# rpi_hat.net
KiCad netlist of a schematic drawn in EAGLE
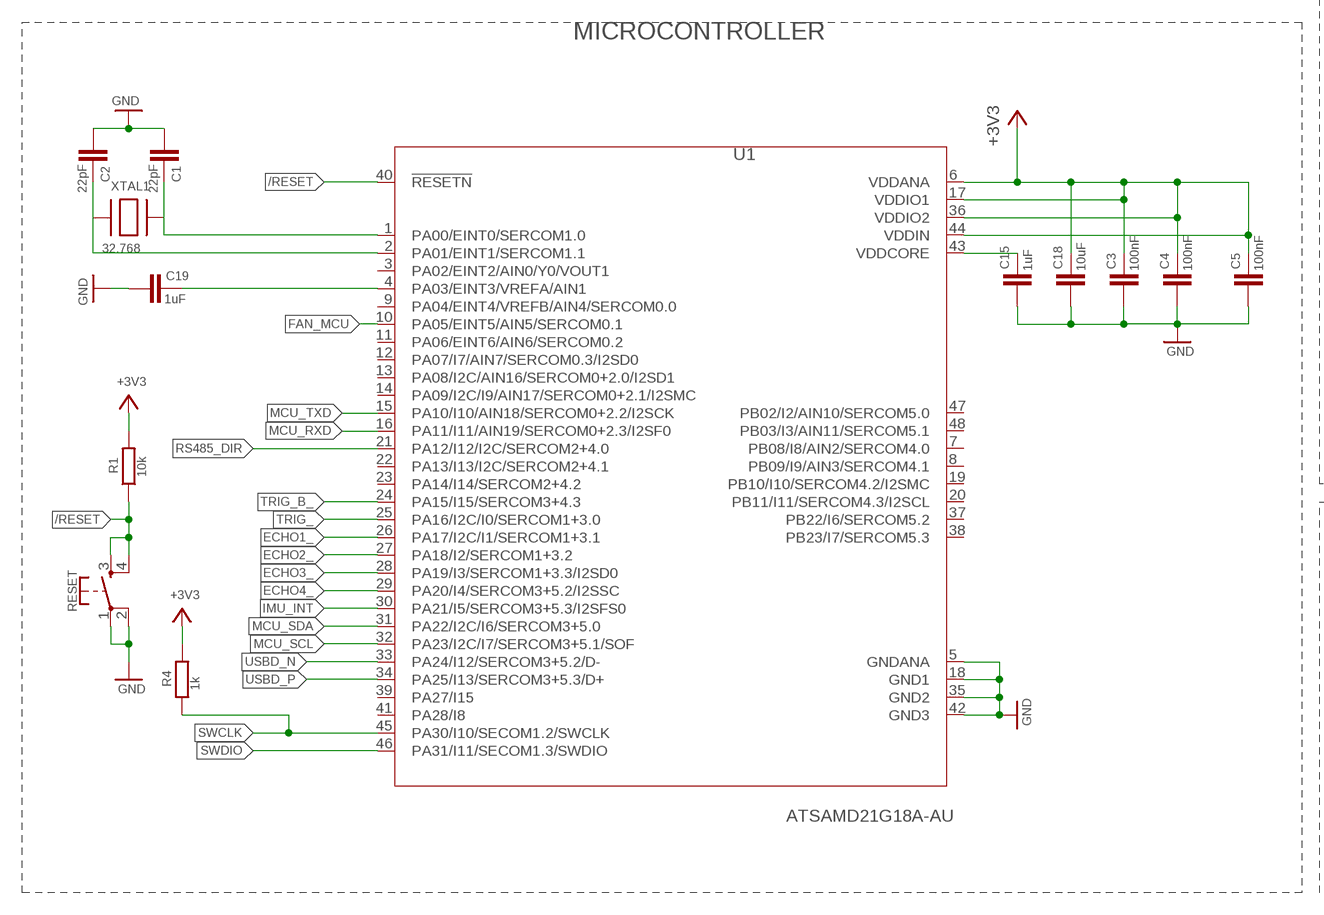
[diagram p0: schematic, sheet 1, part 1 of 2]
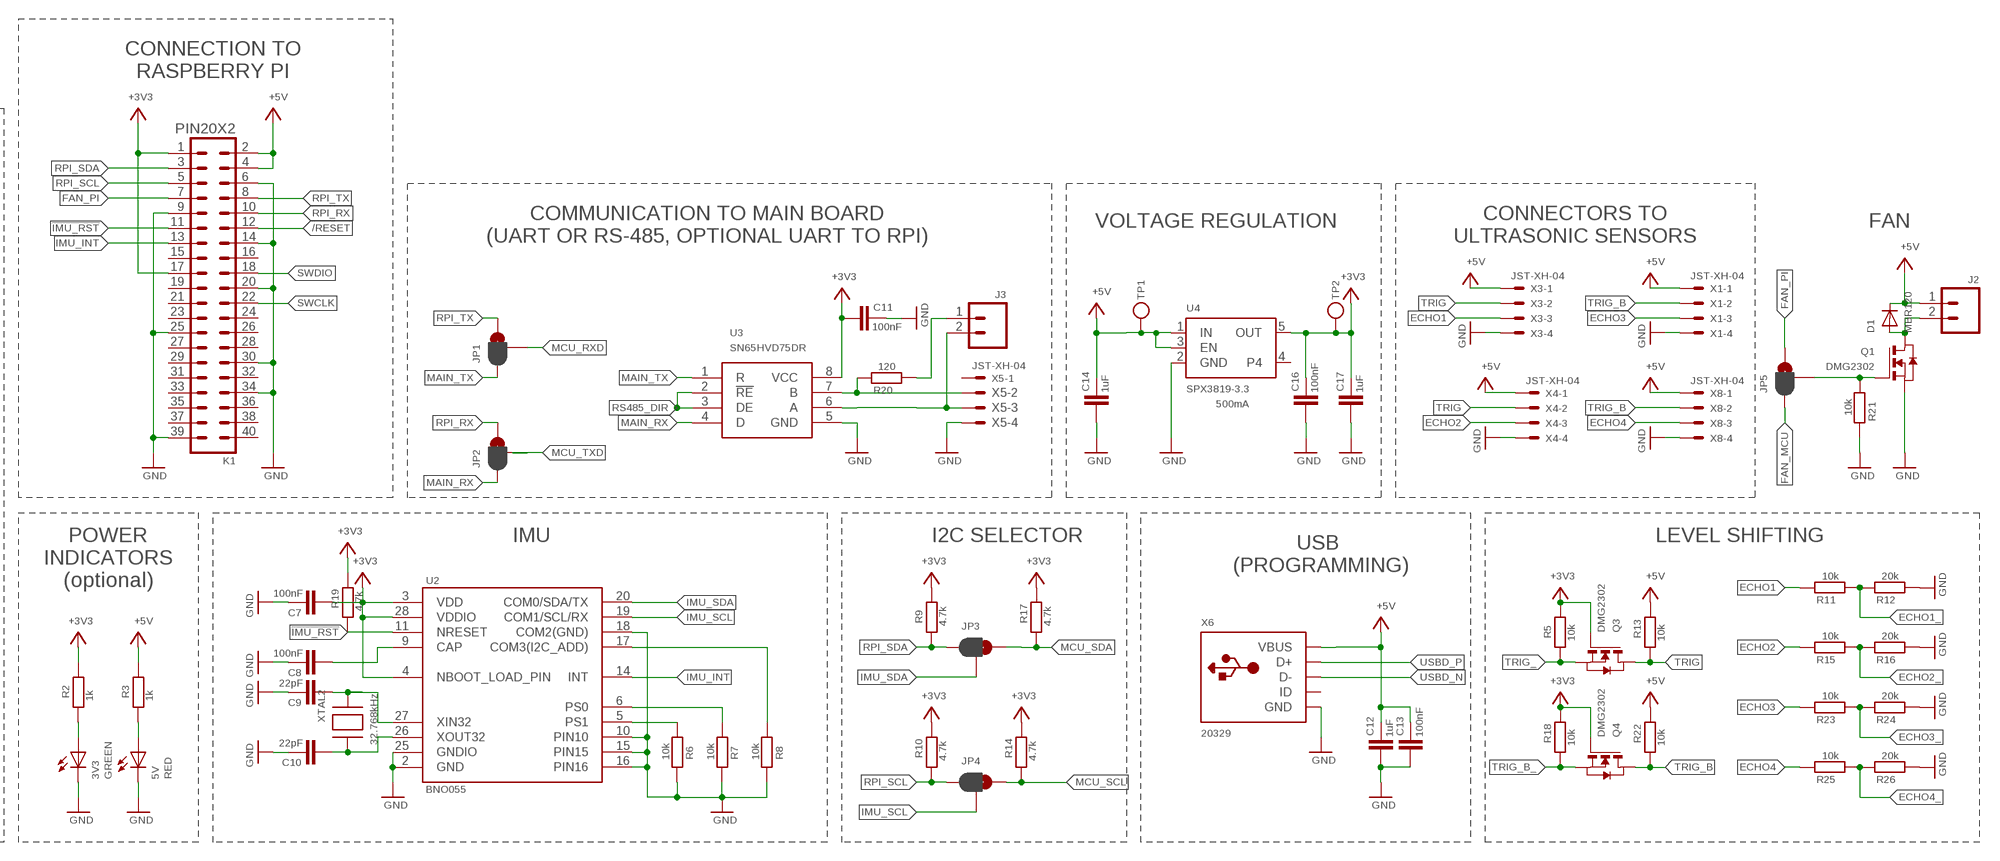
[diagram p1: schematic, sheet 1, part 2 of 2]

(export (version "E")
  (design (tool "Eeschema 10.0.6"))
  (components
    (comp (ref "3V3")
      (value "GREEN")
      (footprint "eagle-import:CHIP-LED0603")
      (libsource (lib "eagle-import") (part "LEDCHIP-LED0603"))
    )
    (comp (ref "5V")
      (value "RED")
      (footprint "eagle-import:CHIP-LED0603")
      (libsource (lib "eagle-import") (part "LEDCHIP-LED0603"))
    )
    (comp (ref "C1")
      (value "22pF")
      (footprint "eagle-import:C0402")
      (libsource (lib "eagle-import") (part "C-EUC0402"))
    )
    (comp (ref "C2")
      (value "22pF")
      (footprint "eagle-import:C0402")
      (libsource (lib "eagle-import") (part "C-EUC0402"))
    )
    (comp (ref "C3")
      (value "100nF")
      (footprint "eagle-import:C0402")
      (libsource (lib "eagle-import") (part "C-EUC0402"))
    )
    (comp (ref "C4")
      (value "100nF")
      (footprint "eagle-import:C0402")
      (libsource (lib "eagle-import") (part "C-EUC0402"))
    )
    (comp (ref "C5")
      (value "100nF")
      (footprint "eagle-import:C0402")
      (libsource (lib "eagle-import") (part "C-EUC0402"))
    )
    (comp (ref "C7")
      (value "100nF")
      (footprint "eagle-import:C0402")
      (libsource (lib "eagle-import") (part "C-EUC0402"))
    )
    (comp (ref "C8")
      (value "100nF")
      (footprint "eagle-import:C0402")
      (libsource (lib "eagle-import") (part "C-EUC0402"))
    )
    (comp (ref "C9")
      (value "22pF")
      (footprint "eagle-import:C0402")
      (libsource (lib "eagle-import") (part "C-EUC0402"))
    )
    (comp (ref "C10")
      (value "22pF")
      (footprint "eagle-import:C0402")
      (libsource (lib "eagle-import") (part "C-EUC0402"))
    )
    (comp (ref "C11")
      (value "100nF")
      (footprint "eagle-import:C0402")
      (libsource (lib "eagle-import") (part "C-EUC0402"))
    )
    (comp (ref "C12")
      (value "1uF")
      (footprint "eagle-import:C0402")
      (libsource (lib "eagle-import") (part "C-EUC0402"))
    )
    (comp (ref "C13")
      (value "100nF")
      (footprint "eagle-import:C0402")
      (libsource (lib "eagle-import") (part "C-EUC0402"))
    )
    (comp (ref "C14")
      (value "1uF")
      (footprint "eagle-import:C0402")
      (libsource (lib "eagle-import") (part "C-EUC0402"))
    )
    (comp (ref "C15")
      (value "1uF")
      (footprint "eagle-import:C0402")
      (libsource (lib "eagle-import") (part "C-EUC0402"))
    )
    (comp (ref "C16")
      (value "100nF")
      (footprint "eagle-import:C0402")
      (libsource (lib "eagle-import") (part "C-EUC0402"))
    )
    (comp (ref "C17")
      (value "1uF")
      (footprint "eagle-import:C0402")
      (libsource (lib "eagle-import") (part "C-EUC0402"))
    )
    (comp (ref "C18")
      (value "10uF")
      (footprint "eagle-import:C0402")
      (libsource (lib "eagle-import") (part "C-EUC0402"))
    )
    (comp (ref "C19")
      (value "1uF")
      (footprint "eagle-import:C0402")
      (libsource (lib "eagle-import") (part "C-EUC0402"))
    )
    (comp (ref "D1")
      (value "MBR120")
      (footprint "eagle-import:SOD-123")
      (libsource (lib "eagle-import") (part "DIODESOD-123"))
    )
    (comp (ref "J2")
      (value "CONN_02")
      (footprint "eagle-import:1X02")
      (libsource (lib "eagle-import") (part "CONN_02"))
    )
    (comp (ref "J3")
      (value "CONN_02")
      (footprint "eagle-import:1X02")
      (libsource (lib "eagle-import") (part "CONN_02"))
    )
    (comp (ref "JP1")
      (value "SPARKFUN-PASSIVES_JUMPER_PAD-3-1&2_NC_BY_PASTE")
      (footprint "eagle-import:SPARKFUN-PASSIVES_PAD-HUMPER-3-1&2_NC_BY_PASTE_YES_SILK_FULL_BOX")
      (libsource (lib "eagle-import") (part "SPARKFUN-PASSIVES_JUMPER_PAD-3-1&2_NC_BY_PASTE"))
    )
    (comp (ref "JP2")
      (value "SPARKFUN-PASSIVES_JUMPER_PAD-3-1&2_NC_BY_PASTE")
      (footprint "eagle-import:SPARKFUN-PASSIVES_PAD-HUMPER-3-1&2_NC_BY_PASTE_YES_SILK_FULL_BOX")
      (libsource (lib "eagle-import") (part "SPARKFUN-PASSIVES_JUMPER_PAD-3-1&2_NC_BY_PASTE"))
    )
    (comp (ref "JP3")
      (value "SPARKFUN-PASSIVES_JUMPER_PAD-3-1&2_NC_BY_PASTE")
      (footprint "eagle-import:SPARKFUN-PASSIVES_PAD-HUMPER-3-1&2_NC_BY_PASTE_YES_SILK_FULL_BOX")
      (libsource (lib "eagle-import") (part "SPARKFUN-PASSIVES_JUMPER_PAD-3-1&2_NC_BY_PASTE"))
    )
    (comp (ref "JP4")
      (value "SPARKFUN-PASSIVES_JUMPER_PAD-3-1&2_NC_BY_PASTE")
      (footprint "eagle-import:SPARKFUN-PASSIVES_PAD-HUMPER-3-1&2_NC_BY_PASTE_YES_SILK_FULL_BOX")
      (libsource (lib "eagle-import") (part "SPARKFUN-PASSIVES_JUMPER_PAD-3-1&2_NC_BY_PASTE"))
    )
    (comp (ref "JP5")
      (value "SPARKFUN-PASSIVES_JUMPER_PAD-3-1&2_NC_BY_PASTE")
      (footprint "eagle-import:SPARKFUN-PASSIVES_PAD-HUMPER-3-1&2_NC_BY_PASTE_YES_SILK_FULL_BOX")
      (libsource (lib "eagle-import") (part "SPARKFUN-PASSIVES_JUMPER_PAD-3-1&2_NC_BY_PASTE"))
    )
    (comp (ref "K1")
      (value "PIN20X2")
      (footprint "eagle-import:PIN_20X2")
      (libsource (lib "eagle-import") (part "PIN20X2"))
    )
    (comp (ref "Q1")
      (value "DMG2302")
      (footprint "eagle-import:SOT-23")
      (libsource (lib "eagle-import") (part "NMOS-SOT23"))
    )
    (comp (ref "Q3")
      (value "DMG2302")
      (footprint "eagle-import:SOT-23")
      (libsource (lib "eagle-import") (part "NMOS-SOT23"))
    )
    (comp (ref "Q4")
      (value "DMG2302")
      (footprint "eagle-import:SOT-23")
      (libsource (lib "eagle-import") (part "NMOS-SOT23"))
    )
    (comp (ref "R1")
      (value "10k")
      (footprint "eagle-import:R0402")
      (libsource (lib "eagle-import") (part "R-EU_R0402"))
    )
    (comp (ref "R2")
      (value "1k")
      (footprint "eagle-import:R0402")
      (libsource (lib "eagle-import") (part "R-EU_R0402"))
    )
    (comp (ref "R3")
      (value "1k")
      (footprint "eagle-import:R0402")
      (libsource (lib "eagle-import") (part "R-EU_R0402"))
    )
    (comp (ref "R4")
      (value "1k")
      (footprint "eagle-import:R0402")
      (libsource (lib "eagle-import") (part "R-EU_R0402"))
    )
    (comp (ref "R5")
      (value "10k")
      (footprint "eagle-import:R0402")
      (libsource (lib "eagle-import") (part "R-EU_R0402"))
    )
    (comp (ref "R6")
      (value "10k")
      (footprint "eagle-import:R0402")
      (libsource (lib "eagle-import") (part "R-EU_R0402"))
    )
    (comp (ref "R7")
      (value "10k")
      (footprint "eagle-import:R0402")
      (libsource (lib "eagle-import") (part "R-EU_R0402"))
    )
    (comp (ref "R8")
      (value "10k")
      (footprint "eagle-import:R0402")
      (libsource (lib "eagle-import") (part "R-EU_R0402"))
    )
    (comp (ref "R9")
      (value "4.7k")
      (footprint "eagle-import:R0402")
      (libsource (lib "eagle-import") (part "R-EU_R0402"))
    )
    (comp (ref "R10")
      (value "4.7k")
      (footprint "eagle-import:R0402")
      (libsource (lib "eagle-import") (part "R-EU_R0402"))
    )
    (comp (ref "R11")
      (value "10k")
      (footprint "eagle-import:R0402")
      (libsource (lib "eagle-import") (part "R-EU_R0402"))
    )
    (comp (ref "R12")
      (value "20k")
      (footprint "eagle-import:R0402")
      (libsource (lib "eagle-import") (part "R-EU_R0402"))
    )
    (comp (ref "R13")
      (value "10k")
      (footprint "eagle-import:R0402")
      (libsource (lib "eagle-import") (part "R-EU_R0402"))
    )
    (comp (ref "R14")
      (value "4.7k")
      (footprint "eagle-import:R0402")
      (libsource (lib "eagle-import") (part "R-EU_R0402"))
    )
    (comp (ref "R15")
      (value "10k")
      (footprint "eagle-import:R0402")
      (libsource (lib "eagle-import") (part "R-EU_R0402"))
    )
    (comp (ref "R16")
      (value "20k")
      (footprint "eagle-import:R0402")
      (libsource (lib "eagle-import") (part "R-EU_R0402"))
    )
    (comp (ref "R17")
      (value "4.7k")
      (footprint "eagle-import:R0402")
      (libsource (lib "eagle-import") (part "R-EU_R0402"))
    )
    (comp (ref "R18")
      (value "10k")
      (footprint "eagle-import:R0402")
      (libsource (lib "eagle-import") (part "R-EU_R0402"))
    )
    (comp (ref "R19")
      (value "4.7k")
      (footprint "eagle-import:R0402")
      (libsource (lib "eagle-import") (part "R-EU_R0402"))
    )
    (comp (ref "R20")
      (value "120")
      (footprint "eagle-import:R0402")
      (libsource (lib "eagle-import") (part "R-EU_R0402"))
    )
    (comp (ref "R21")
      (value "10k")
      (footprint "eagle-import:R0402")
      (libsource (lib "eagle-import") (part "R-EU_R0402"))
    )
    (comp (ref "R22")
      (value "10k")
      (footprint "eagle-import:R0402")
      (libsource (lib "eagle-import") (part "R-EU_R0402"))
    )
    (comp (ref "R23")
      (value "10k")
      (footprint "eagle-import:R0402")
      (libsource (lib "eagle-import") (part "R-EU_R0402"))
    )
    (comp (ref "R24")
      (value "20k")
      (footprint "eagle-import:R0402")
      (libsource (lib "eagle-import") (part "R-EU_R0402"))
    )
    (comp (ref "R25")
      (value "10k")
      (footprint "eagle-import:R0402")
      (libsource (lib "eagle-import") (part "R-EU_R0402"))
    )
    (comp (ref "R26")
      (value "20k")
      (footprint "eagle-import:R0402")
      (libsource (lib "eagle-import") (part "R-EU_R0402"))
    )
    (comp (ref "RESET")
      (value "MOMENTARY-SWITCH-SPST-2-SMD-4.6X2.8MM")
      (footprint "eagle-import:TACTILE_SWITCH_SMD_4.6X2.8MM")
      (libsource (lib "eagle-import") (part "MOMENTARY-SWITCH-SPST-2-SMD-4.6X2.8MM"))
    )
    (comp (ref "TP1")
      (value "MICROBUILDER_TESTPOINTROUND1MM")
      (footprint "eagle-import:MICROBUILDER_TESTPOINT_ROUND_1MM")
      (libsource (lib "eagle-import") (part "MICROBUILDER_TESTPOINTROUND1MM"))
    )
    (comp (ref "TP2")
      (value "MICROBUILDER_TESTPOINTROUND1MM")
      (footprint "eagle-import:MICROBUILDER_TESTPOINT_ROUND_1MM")
      (libsource (lib "eagle-import") (part "MICROBUILDER_TESTPOINTROUND1MM"))
    )
    (comp (ref "U1")
      (value "ATSAMD21G18A-AU")
      (footprint "eagle-import:QFP50P900X900X120-48N")
      (fields (field (name "MF") "Microchip"))
      (libsource (lib "eagle-import") (part "ATSAMD21G18A-AU"))
    )
    (comp (ref "U2")
      (value "BNO055")
      (footprint "eagle-import:LGA28R50P4X10_380X520X100")
      (fields (field (name "MF") "Bosch"))
      (libsource (lib "eagle-import") (part "BNO055"))
    )
    (comp (ref "U3")
      (value "SN65HVD75DR")
      (footprint "eagle-import:SOIC127P600X175-8N")
      (fields (field (name "MF") "Texas Instruments"))
      (libsource (lib "eagle-import") (part "SN65HVD75DR"))
    )
    (comp (ref "U4")
      (value "SPX3819-3.3")
      (footprint "eagle-import:SOT23-5")
      (libsource (lib "eagle-import") (part "VREG_SOT23-5"))
    )
    (comp (ref "X1")
      (value "JST-XH-04")
      (footprint "eagle-import:JST-XH-04-PACKAGE-ROUND-PAD")
      (libsource (lib "eagle-import") (part "JST-XH-04-PIN-ROUND-PAD"))
    )
    (comp (ref "X3")
      (value "JST-XH-04")
      (footprint "eagle-import:JST-XH-04-PACKAGE-ROUND-PAD")
      (libsource (lib "eagle-import") (part "JST-XH-04-PIN-ROUND-PAD"))
    )
    (comp (ref "X4")
      (value "JST-XH-04")
      (footprint "eagle-import:JST-XH-04-PACKAGE-ROUND-PAD")
      (libsource (lib "eagle-import") (part "JST-XH-04-PIN-ROUND-PAD"))
    )
    (comp (ref "X5")
      (value "JST-XH-04")
      (footprint "eagle-import:JST-XH-04-PACKAGE-ROUND-PAD")
      (libsource (lib "eagle-import") (part "JST-XH-04-PIN-ROUND-PAD"))
    )
    (comp (ref "X6")
      (value "20329")
      (footprint "eagle-import:4UCONN_20329_V2")
      (libsource (lib "eagle-import") (part "USB_MICRO_20329_V2"))
    )
    (comp (ref "X8")
      (value "JST-XH-04")
      (footprint "eagle-import:JST-XH-04-PACKAGE-ROUND-PAD")
      (libsource (lib "eagle-import") (part "JST-XH-04-PIN-ROUND-PAD"))
    )
    (comp (ref "XTAL1")
      (value "32.768")
      (footprint "eagle-import:XTAL3215")
      (libsource (lib "eagle-import") (part "XTAL-3.2X1.5"))
    )
    (comp (ref "XTAL2")
      (value "32.768kHz")
      (footprint "eagle-import:ADAFRUIT2_XTAL3215")
      (libsource (lib "eagle-import") (part "ADAFRUIT2_XTAL-3.2X1.5"))
    )
  )
  (nets
    (net (code "1") (name "+3V3") (class "Default")
      (node (ref "C11") (pin "2") (pinfunction "2_2") (pintype "passive"))
      (node (ref "C16") (pin "1") (pinfunction "1_1") (pintype "passive"))
      (node (ref "C17") (pin "1") (pinfunction "1_1") (pintype "passive"))
      (node (ref "C18") (pin "1") (pinfunction "1_1") (pintype "passive"))
      (node (ref "C3") (pin "1") (pinfunction "1_1") (pintype "passive"))
      (node (ref "C4") (pin "1") (pinfunction "1_1") (pintype "passive"))
      (node (ref "C5") (pin "1") (pinfunction "1_1") (pintype "passive"))
      (node (ref "C7") (pin "2") (pinfunction "2_2") (pintype "passive"))
      (node (ref "K1") (pin "1") (pinfunction "1_1") (pintype "passive"))
      (node (ref "K1") (pin "17") (pinfunction "17_17") (pintype "passive"))
      (node (ref "Q3") (pin "G") (pinfunction "G_G") (pintype "passive"))
      (node (ref "Q4") (pin "G") (pinfunction "G_G") (pintype "passive"))
      (node (ref "R1") (pin "2") (pinfunction "2_2") (pintype "passive"))
      (node (ref "R10") (pin "2") (pinfunction "2_2") (pintype "passive"))
      (node (ref "R14") (pin "2") (pinfunction "2_2") (pintype "passive"))
      (node (ref "R17") (pin "2") (pinfunction "2_2") (pintype "passive"))
      (node (ref "R18") (pin "2") (pinfunction "2_2") (pintype "passive"))
      (node (ref "R19") (pin "2") (pinfunction "2_2") (pintype "passive"))
      (node (ref "R2") (pin "2") (pinfunction "2_2") (pintype "passive"))
      (node (ref "R4") (pin "2") (pinfunction "2_2") (pintype "passive"))
      (node (ref "R5") (pin "2") (pinfunction "2_2") (pintype "passive"))
      (node (ref "R9") (pin "2") (pinfunction "2_2") (pintype "passive"))
      (node (ref "TP2") (pin "P$1") (pinfunction "P$1_P$1") (pintype "bidirectional"))
      (node (ref "U1") (pin "17") (pinfunction "VDDIO1_17") (pintype "power_in"))
      (node (ref "U1") (pin "36") (pinfunction "VDDIO2_36") (pintype "power_in"))
      (node (ref "U1") (pin "44") (pinfunction "VDDIN_44") (pintype "power_in"))
      (node (ref "U1") (pin "6") (pinfunction "VDDANA_6") (pintype "power_in"))
      (node (ref "U2") (pin "28") (pinfunction "VDDIO_28") (pintype "power_in"))
      (node (ref "U2") (pin "3") (pinfunction "VDD_3") (pintype "power_in"))
      (node (ref "U2") (pin "4") (pinfunction "NBOOT_LOAD_PIN_4") (pintype "bidirectional"))
      (node (ref "U3") (pin "8") (pinfunction "VCC_8") (pintype "bidirectional"))
      (node (ref "U4") (pin "5") (pinfunction "OUT_5") (pintype "power_in"))
    )
    (net (code "2") (name "+5V") (class "Default")
      (node (ref "C12") (pin "1") (pinfunction "1_1") (pintype "passive"))
      (node (ref "C13") (pin "1") (pinfunction "1_1") (pintype "passive"))
      (node (ref "C14") (pin "1") (pinfunction "1_1") (pintype "passive"))
      (node (ref "D1") (pin "C") (pinfunction "C_C") (pintype "passive"))
      (node (ref "J2") (pin "1") (pinfunction "1_1") (pintype "passive"))
      (node (ref "K1") (pin "2") (pinfunction "2_2") (pintype "passive"))
      (node (ref "K1") (pin "4") (pinfunction "4_4") (pintype "passive"))
      (node (ref "R13") (pin "2") (pinfunction "2_2") (pintype "passive"))
      (node (ref "R22") (pin "2") (pinfunction "2_2") (pintype "passive"))
      (node (ref "R3") (pin "2") (pinfunction "2_2") (pintype "passive"))
      (node (ref "TP1") (pin "P$1") (pinfunction "P$1_P$1") (pintype "bidirectional"))
      (node (ref "U4") (pin "1") (pinfunction "IN_1") (pintype "power_in"))
      (node (ref "U4") (pin "3") (pinfunction "EN_3") (pintype "input"))
      (node (ref "X1") (pin "1") (pinfunction "S_1") (pintype "passive"))
      (node (ref "X3") (pin "1") (pinfunction "S_1") (pintype "passive"))
      (node (ref "X4") (pin "1") (pinfunction "S_1") (pintype "passive"))
      (node (ref "X6") (pin "VBUS") (pinfunction "VBUS_VBUS") (pintype "power_in"))
      (node (ref "X8") (pin "1") (pinfunction "S_1") (pintype "passive"))
    )
    (net (code "3") (name "/~{IMU_RST}") (class "Default")
      (node (ref "K1") (pin "11") (pinfunction "11_11") (pintype "passive"))
      (node (ref "R19") (pin "1") (pinfunction "1_1") (pintype "passive"))
      (node (ref "U2") (pin "11") (pinfunction "NRESET_11") (pintype "input"))
    )
    (net (code "4") (name "ECHO1") (class "Default")
      (node (ref "R11") (pin "2") (pinfunction "2_2") (pintype "passive"))
      (node (ref "X3") (pin "3") (pinfunction "S_3") (pintype "passive"))
    )
    (net (code "5") (name "ECHO1_") (class "Default")
      (node (ref "R11") (pin "1") (pinfunction "1_1") (pintype "passive"))
      (node (ref "R12") (pin "2") (pinfunction "2_2") (pintype "passive"))
      (node (ref "U1") (pin "26") (pinfunction "PA17/I2C/I1/SERCOM1+3.1_26") (pintype "bidirectional"))
    )
    (net (code "6") (name "ECHO2") (class "Default")
      (node (ref "R15") (pin "2") (pinfunction "2_2") (pintype "passive"))
      (node (ref "X4") (pin "3") (pinfunction "S_3") (pintype "passive"))
    )
    (net (code "7") (name "ECHO2_") (class "Default")
      (node (ref "R15") (pin "1") (pinfunction "1_1") (pintype "passive"))
      (node (ref "R16") (pin "2") (pinfunction "2_2") (pintype "passive"))
      (node (ref "U1") (pin "27") (pinfunction "PA18/I2/SERCOM1+3.2_27") (pintype "bidirectional"))
    )
    (net (code "8") (name "ECHO3") (class "Default")
      (node (ref "R23") (pin "2") (pinfunction "2_2") (pintype "passive"))
      (node (ref "X1") (pin "3") (pinfunction "S_3") (pintype "passive"))
    )
    (net (code "9") (name "ECHO3_") (class "Default")
      (node (ref "R23") (pin "1") (pinfunction "1_1") (pintype "passive"))
      (node (ref "R24") (pin "2") (pinfunction "2_2") (pintype "passive"))
      (node (ref "U1") (pin "28") (pinfunction "PA19/I3/SERCOM1+3.3/I2SD0_28") (pintype "bidirectional"))
    )
    (net (code "10") (name "ECHO4") (class "Default")
      (node (ref "R25") (pin "2") (pinfunction "2_2") (pintype "passive"))
      (node (ref "X8") (pin "3") (pinfunction "S_3") (pintype "passive"))
    )
    (net (code "11") (name "ECHO4_") (class "Default")
      (node (ref "R25") (pin "1") (pinfunction "1_1") (pintype "passive"))
      (node (ref "R26") (pin "2") (pinfunction "2_2") (pintype "passive"))
      (node (ref "U1") (pin "29") (pinfunction "PA20/I4/SERCOM3+5.2/I2SSC_29") (pintype "bidirectional"))
    )
    (net (code "12") (name "FAN_MCU") (class "Default")
      (node (ref "JP5") (pin "1") (pinfunction "1_1") (pintype "passive"))
      (node (ref "U1") (pin "10") (pinfunction "PA05/EINT5/AIN5/SERCOM0.1_10") (pintype "bidirectional"))
    )
    (net (code "13") (name "FAN_PI") (class "Default")
      (node (ref "JP5") (pin "3") (pinfunction "3_3") (pintype "passive"))
      (node (ref "K1") (pin "7") (pinfunction "7_7") (pintype "passive"))
    )
    (net (code "14") (name "GND") (class "Default")
      (node (ref "3V3") (pin "C") (pinfunction "C_C") (pintype "passive"))
      (node (ref "5V") (pin "C") (pinfunction "C_C") (pintype "passive"))
      (node (ref "C1") (pin "2") (pinfunction "2_2") (pintype "passive"))
      (node (ref "C10") (pin "1") (pinfunction "1_1") (pintype "passive"))
      (node (ref "C11") (pin "1") (pinfunction "1_1") (pintype "passive"))
      (node (ref "C12") (pin "2") (pinfunction "2_2") (pintype "passive"))
      (node (ref "C13") (pin "2") (pinfunction "2_2") (pintype "passive"))
      (node (ref "C14") (pin "2") (pinfunction "2_2") (pintype "passive"))
      (node (ref "C15") (pin "2") (pinfunction "2_2") (pintype "passive"))
      (node (ref "C16") (pin "2") (pinfunction "2_2") (pintype "passive"))
      (node (ref "C17") (pin "2") (pinfunction "2_2") (pintype "passive"))
      (node (ref "C18") (pin "2") (pinfunction "2_2") (pintype "passive"))
      (node (ref "C19") (pin "2") (pinfunction "2_2") (pintype "passive"))
      (node (ref "C2") (pin "2") (pinfunction "2_2") (pintype "passive"))
      (node (ref "C3") (pin "2") (pinfunction "2_2") (pintype "passive"))
      (node (ref "C4") (pin "2") (pinfunction "2_2") (pintype "passive"))
      (node (ref "C5") (pin "2") (pinfunction "2_2") (pintype "passive"))
      (node (ref "C7") (pin "1") (pinfunction "1_1") (pintype "passive"))
      (node (ref "C8") (pin "1") (pinfunction "1_1") (pintype "passive"))
      (node (ref "C9") (pin "1") (pinfunction "1_1") (pintype "passive"))
      (node (ref "K1") (pin "14") (pinfunction "14_14") (pintype "passive"))
      (node (ref "K1") (pin "20") (pinfunction "20_20") (pintype "passive"))
      (node (ref "K1") (pin "25") (pinfunction "25_25") (pintype "passive"))
      (node (ref "K1") (pin "30") (pinfunction "30_30") (pintype "passive"))
      (node (ref "K1") (pin "34") (pinfunction "34_34") (pintype "passive"))
      (node (ref "K1") (pin "39") (pinfunction "39_39") (pintype "passive"))
      (node (ref "K1") (pin "6") (pinfunction "6_6") (pintype "passive"))
      (node (ref "K1") (pin "9") (pinfunction "9_9") (pintype "passive"))
      (node (ref "Q1") (pin "S") (pinfunction "S_S") (pintype "passive"))
      (node (ref "R12") (pin "1") (pinfunction "1_1") (pintype "passive"))
      (node (ref "R16") (pin "1") (pinfunction "1_1") (pintype "passive"))
      (node (ref "R21") (pin "2") (pinfunction "2_2") (pintype "passive"))
      (node (ref "R24") (pin "1") (pinfunction "1_1") (pintype "passive"))
      (node (ref "R26") (pin "1") (pinfunction "1_1") (pintype "passive"))
      (node (ref "R6") (pin "2") (pinfunction "2_2") (pintype "passive"))
      (node (ref "R7") (pin "2") (pinfunction "2_2") (pintype "passive"))
      (node (ref "R8") (pin "2") (pinfunction "2_2") (pintype "passive"))
      (node (ref "RESET") (pin "1") (pinfunction "1_1") (pintype "passive"))
      (node (ref "RESET") (pin "2") (pinfunction "2_2") (pintype "passive"))
      (node (ref "U1") (pin "18") (pinfunction "GND1_18") (pintype "power_in"))
      (node (ref "U1") (pin "35") (pinfunction "GND2_35") (pintype "power_in"))
      (node (ref "U1") (pin "42") (pinfunction "GND3_42") (pintype "power_in"))
      (node (ref "U1") (pin "5") (pinfunction "GNDANA_5") (pintype "power_in"))
      (node (ref "U2") (pin "10") (pinfunction "PIN10_10") (pintype "power_in"))
      (node (ref "U2") (pin "15") (pinfunction "PIN15_15") (pintype "power_in"))
      (node (ref "U2") (pin "16") (pinfunction "PIN16_16") (pintype "power_in"))
      (node (ref "U2") (pin "18") (pinfunction "COM2(GND)_18") (pintype "bidirectional"))
      (node (ref "U2") (pin "2") (pinfunction "GND_2") (pintype "power_in"))
      (node (ref "U2") (pin "25") (pinfunction "GNDIO_25") (pintype "power_in"))
      (node (ref "U3") (pin "5") (pinfunction "GND_5") (pintype "bidirectional"))
      (node (ref "U4") (pin "2") (pinfunction "GND_2") (pintype "power_in"))
      (node (ref "X1") (pin "4") (pinfunction "S_4") (pintype "passive"))
      (node (ref "X3") (pin "4") (pinfunction "S_4") (pintype "passive"))
      (node (ref "X4") (pin "4") (pinfunction "S_4") (pintype "passive"))
      (node (ref "X5") (pin "4") (pinfunction "S_4") (pintype "passive"))
      (node (ref "X6") (pin "BASE@1") (pinfunction "GND_BASE@1") (pintype "power_in"))
      (node (ref "X6") (pin "BASE@2") (pinfunction "GND_BASE@2") (pintype "power_in"))
      (node (ref "X6") (pin "GND") (pinfunction "GND_GND") (pintype "power_in"))
      (node (ref "X6") (pin "SPRT@1") (pinfunction "GND_SPRT@1") (pintype "power_in"))
      (node (ref "X6") (pin "SPRT@2") (pinfunction "GND_SPRT@2") (pintype "power_in"))
      (node (ref "X6") (pin "SPRT@3") (pinfunction "GND_SPRT@3") (pintype "power_in"))
      (node (ref "X6") (pin "SPRT@4") (pinfunction "GND_SPRT@4") (pintype "power_in"))
      (node (ref "X8") (pin "4") (pinfunction "S_4") (pintype "passive"))
    )
    (net (code "15") (name "IMU_INT") (class "Default")
      (node (ref "K1") (pin "13") (pinfunction "13_13") (pintype "passive"))
      (node (ref "U1") (pin "30") (pinfunction "PA21/I5/SERCOM3+5.3/I2SFS0_30") (pintype "bidirectional"))
      (node (ref "U2") (pin "14") (pinfunction "INT_14") (pintype "output"))
    )
    (net (code "16") (name "IMU_SCL") (class "Default")
      (node (ref "JP4") (pin "2") (pinfunction "2_2") (pintype "passive"))
      (node (ref "U2") (pin "19") (pinfunction "COM1/SCL/RX_19") (pintype "bidirectional"))
    )
    (net (code "17") (name "IMU_SDA") (class "Default")
      (node (ref "JP3") (pin "2") (pinfunction "2_2") (pintype "passive"))
      (node (ref "U2") (pin "20") (pinfunction "COM0/SDA/TX_20") (pintype "bidirectional"))
    )
    (net (code "18") (name "MAIN_RX") (class "Default")
      (node (ref "JP2") (pin "1") (pinfunction "1_1") (pintype "passive"))
      (node (ref "U3") (pin "4") (pinfunction "D_4") (pintype "bidirectional"))
    )
    (net (code "19") (name "MAIN_TX") (class "Default")
      (node (ref "JP1") (pin "1") (pinfunction "1_1") (pintype "passive"))
      (node (ref "U3") (pin "1") (pinfunction "R_1") (pintype "bidirectional"))
    )
    (net (code "20") (name "MCU_RXD") (class "Default")
      (node (ref "JP1") (pin "2") (pinfunction "2_2") (pintype "passive"))
      (node (ref "U1") (pin "16") (pinfunction "PA11/I11/AIN19/SERCOM0+2.3/I2SF0_16") (pintype "bidirectional"))
    )
    (net (code "21") (name "MCU_SCL") (class "Default")
      (node (ref "JP4") (pin "3") (pinfunction "3_3") (pintype "passive"))
      (node (ref "R14") (pin "1") (pinfunction "1_1") (pintype "passive"))
      (node (ref "U1") (pin "32") (pinfunction "PA23/I2C/I7/SERCOM3+5.1/SOF_32") (pintype "bidirectional"))
    )
    (net (code "22") (name "MCU_SDA") (class "Default")
      (node (ref "JP3") (pin "3") (pinfunction "3_3") (pintype "passive"))
      (node (ref "R17") (pin "1") (pinfunction "1_1") (pintype "passive"))
      (node (ref "U1") (pin "31") (pinfunction "PA22/I2C/I6/SERCOM3+5.0_31") (pintype "bidirectional"))
    )
    (net (code "23") (name "MCU_TXD") (class "Default")
      (node (ref "JP2") (pin "2") (pinfunction "2_2") (pintype "passive"))
      (node (ref "U1") (pin "15") (pinfunction "PA10/I10/AIN18/SERCOM0+2.2/I2SCK_15") (pintype "bidirectional"))
    )
    (net (code "24") (name "Net-(3V3-PadA)") (class "Default")
      (node (ref "3V3") (pin "A") (pinfunction "A_A") (pintype "passive"))
      (node (ref "R2") (pin "1") (pinfunction "1_1") (pintype "passive"))
    )
    (net (code "25") (name "Net-(5V-PadA)") (class "Default")
      (node (ref "5V") (pin "A") (pinfunction "A_A") (pintype "passive"))
      (node (ref "R3") (pin "1") (pinfunction "1_1") (pintype "passive"))
    )
    (net (code "26") (name "Net-(D1-PadA)") (class "Default")
      (node (ref "D1") (pin "A") (pinfunction "A_A") (pintype "passive"))
      (node (ref "J2") (pin "2") (pinfunction "2_2") (pintype "passive"))
      (node (ref "Q1") (pin "D") (pinfunction "D_D") (pintype "passive"))
    )
    (net (code "27") (name "Net-(J3-Pad1)") (class "Default")
      (node (ref "J3") (pin "1") (pinfunction "1_1") (pintype "passive"))
      (node (ref "R20") (pin "1") (pinfunction "1_1") (pintype "passive"))
    )
    (net (code "28") (name "Net-(JP5-Pad2)") (class "Default")
      (node (ref "JP5") (pin "2") (pinfunction "2_2") (pintype "passive"))
      (node (ref "Q1") (pin "G") (pinfunction "G_G") (pintype "passive"))
      (node (ref "R21") (pin "1") (pinfunction "1_1") (pintype "passive"))
    )
    (net (code "29") (name "Net-(U1-PA00{slash}EINT0{slash}SERCOM1.0)") (class "Default")
      (node (ref "C1") (pin "1") (pinfunction "1_1") (pintype "passive"))
      (node (ref "U1") (pin "1") (pinfunction "PA00/EINT0/SERCOM1.0_1") (pintype "bidirectional"))
      (node (ref "XTAL1") (pin "P$2") (pinfunction "P$2_P$2") (pintype "bidirectional"))
    )
    (net (code "30") (name "Net-(U1-PA01{slash}EINT1{slash}SERCOM1.1)") (class "Default")
      (node (ref "C2") (pin "1") (pinfunction "1_1") (pintype "passive"))
      (node (ref "U1") (pin "2") (pinfunction "PA01/EINT1/SERCOM1.1_2") (pintype "bidirectional"))
      (node (ref "XTAL1") (pin "P$1") (pinfunction "P$1_P$1") (pintype "bidirectional"))
    )
    (net (code "31") (name "Net-(U1-PA03{slash}EINT3{slash}VREFA{slash}AIN1)") (class "Default")
      (node (ref "C19") (pin "1") (pinfunction "1_1") (pintype "passive"))
      (node (ref "U1") (pin "4") (pinfunction "PA03/EINT3/VREFA/AIN1_4") (pintype "bidirectional"))
    )
    (net (code "32") (name "Net-(U1-VDDCORE)") (class "Default")
      (node (ref "C15") (pin "1") (pinfunction "1_1") (pintype "passive"))
      (node (ref "U1") (pin "43") (pinfunction "VDDCORE_43") (pintype "power_in"))
    )
    (net (code "33") (name "Net-(U2-CAP)") (class "Default")
      (node (ref "C8") (pin "2") (pinfunction "2_2") (pintype "passive"))
      (node (ref "U2") (pin "9") (pinfunction "CAP_9") (pintype "passive"))
    )
    (net (code "34") (name "Net-(U2-COM3(I2C_ADD))") (class "Default")
      (node (ref "R8") (pin "1") (pinfunction "1_1") (pintype "passive"))
      (node (ref "U2") (pin "17") (pinfunction "COM3(I2C_ADD)_17") (pintype "bidirectional"))
    )
    (net (code "35") (name "Net-(U2-PS0)") (class "Default")
      (node (ref "R7") (pin "1") (pinfunction "1_1") (pintype "passive"))
      (node (ref "U2") (pin "6") (pinfunction "PS0_6") (pintype "input"))
    )
    (net (code "36") (name "Net-(U2-PS1)") (class "Default")
      (node (ref "R6") (pin "1") (pinfunction "1_1") (pintype "passive"))
      (node (ref "U2") (pin "5") (pinfunction "PS1_5") (pintype "input"))
    )
    (net (code "37") (name "Net-(U2-XIN32)") (class "Default")
      (node (ref "C9") (pin "2") (pinfunction "2_2") (pintype "passive"))
      (node (ref "U2") (pin "27") (pinfunction "XIN32_27") (pintype "input"))
      (node (ref "XTAL2") (pin "P$2") (pinfunction "P$2_P$2") (pintype "bidirectional"))
    )
    (net (code "38") (name "Net-(U2-XOUT32)") (class "Default")
      (node (ref "C10") (pin "2") (pinfunction "2_2") (pintype "passive"))
      (node (ref "U2") (pin "26") (pinfunction "XOUT32_26") (pintype "output"))
      (node (ref "XTAL2") (pin "P$1") (pinfunction "P$1_P$1") (pintype "bidirectional"))
    )
    (net (code "39") (name "Net-(U3-A)") (class "Default")
      (node (ref "J3") (pin "2") (pinfunction "2_2") (pintype "passive"))
      (node (ref "U3") (pin "6") (pinfunction "A_6") (pintype "bidirectional"))
      (node (ref "X5") (pin "3") (pinfunction "S_3") (pintype "passive"))
    )
    (net (code "40") (name "Net-(U3-B)") (class "Default")
      (node (ref "R20") (pin "2") (pinfunction "2_2") (pintype "passive"))
      (node (ref "U3") (pin "7") (pinfunction "B_7") (pintype "bidirectional"))
      (node (ref "X5") (pin "2") (pinfunction "S_2") (pintype "passive"))
    )
    (net (code "41") (name "RPI_RX") (class "Default")
      (node (ref "JP2") (pin "3") (pinfunction "3_3") (pintype "passive"))
      (node (ref "K1") (pin "10") (pinfunction "10_10") (pintype "passive"))
    )
    (net (code "42") (name "RPI_SCL") (class "Default")
      (node (ref "JP4") (pin "1") (pinfunction "1_1") (pintype "passive"))
      (node (ref "K1") (pin "5") (pinfunction "5_5") (pintype "passive"))
      (node (ref "R10") (pin "1") (pinfunction "1_1") (pintype "passive"))
    )
    (net (code "43") (name "RPI_SDA") (class "Default")
      (node (ref "JP3") (pin "1") (pinfunction "1_1") (pintype "passive"))
      (node (ref "K1") (pin "3") (pinfunction "3_3") (pintype "passive"))
      (node (ref "R9") (pin "1") (pinfunction "1_1") (pintype "passive"))
    )
    (net (code "44") (name "RPI_TX") (class "Default")
      (node (ref "JP1") (pin "3") (pinfunction "3_3") (pintype "passive"))
      (node (ref "K1") (pin "8") (pinfunction "8_8") (pintype "passive"))
    )
    (net (code "45") (name "RS485_DIR") (class "Default")
      (node (ref "U1") (pin "21") (pinfunction "PA12/I12/I2C/SERCOM2+4.0_21") (pintype "bidirectional"))
      (node (ref "U3") (pin "2") (pinfunction "~{RE}_2") (pintype "bidirectional"))
      (node (ref "U3") (pin "3") (pinfunction "DE_3") (pintype "bidirectional"))
    )
    (net (code "46") (name "SWCLK") (class "Default")
      (node (ref "K1") (pin "22") (pinfunction "22_22") (pintype "passive"))
      (node (ref "R4") (pin "1") (pinfunction "1_1") (pintype "passive"))
      (node (ref "U1") (pin "45") (pinfunction "PA30/I10/SECOM1.2/SWCLK_45") (pintype "bidirectional"))
    )
    (net (code "47") (name "SWDIO") (class "Default")
      (node (ref "K1") (pin "18") (pinfunction "18_18") (pintype "passive"))
      (node (ref "U1") (pin "46") (pinfunction "PA31/I11/SECOM1.3/SWDIO_46") (pintype "bidirectional"))
    )
    (net (code "48") (name "TRIG") (class "Default")
      (node (ref "Q3") (pin "D") (pinfunction "D_D") (pintype "passive"))
      (node (ref "R13") (pin "1") (pinfunction "1_1") (pintype "passive"))
      (node (ref "X3") (pin "2") (pinfunction "S_2") (pintype "passive"))
      (node (ref "X4") (pin "2") (pinfunction "S_2") (pintype "passive"))
    )
    (net (code "49") (name "TRIG_") (class "Default")
      (node (ref "Q3") (pin "S") (pinfunction "S_S") (pintype "passive"))
      (node (ref "R5") (pin "1") (pinfunction "1_1") (pintype "passive"))
      (node (ref "U1") (pin "25") (pinfunction "PA16/I2C/I0/SERCOM1+3.0_25") (pintype "bidirectional"))
    )
    (net (code "50") (name "TRIG_B") (class "Default")
      (node (ref "Q4") (pin "D") (pinfunction "D_D") (pintype "passive"))
      (node (ref "R22") (pin "1") (pinfunction "1_1") (pintype "passive"))
      (node (ref "X1") (pin "2") (pinfunction "S_2") (pintype "passive"))
      (node (ref "X8") (pin "2") (pinfunction "S_2") (pintype "passive"))
    )
    (net (code "51") (name "TRIG_B_") (class "Default")
      (node (ref "Q4") (pin "S") (pinfunction "S_S") (pintype "passive"))
      (node (ref "R18") (pin "1") (pinfunction "1_1") (pintype "passive"))
      (node (ref "U1") (pin "24") (pinfunction "PA15/I15/SERCOM3+4.3_24") (pintype "bidirectional"))
    )
    (net (code "52") (name "USBD_N") (class "Default")
      (node (ref "U1") (pin "33") (pinfunction "PA24/I12/SERCOM3+5.2/D-_33") (pintype "bidirectional"))
      (node (ref "X6") (pin "D-") (pinfunction "D-_D-") (pintype "bidirectional"))
    )
    (net (code "53") (name "USBD_P") (class "Default")
      (node (ref "U1") (pin "34") (pinfunction "PA25/I13/SERCOM3+5.3/D+_34") (pintype "bidirectional"))
      (node (ref "X6") (pin "D+") (pinfunction "D+_D+") (pintype "bidirectional"))
    )
    (net (code "54") (name "unconnected-(K1-Pad15)") (class "Default")
      (node (ref "K1") (pin "15") (pinfunction "15_15") (pintype "passive"))
    )
    (net (code "55") (name "unconnected-(K1-Pad16)") (class "Default")
      (node (ref "K1") (pin "16") (pinfunction "16_16") (pintype "passive"))
    )
    (net (code "56") (name "unconnected-(K1-Pad19)") (class "Default")
      (node (ref "K1") (pin "19") (pinfunction "19_19") (pintype "passive"))
    )
    (net (code "57") (name "unconnected-(K1-Pad21)") (class "Default")
      (node (ref "K1") (pin "21") (pinfunction "21_21") (pintype "passive"))
    )
    (net (code "58") (name "unconnected-(K1-Pad23)") (class "Default")
      (node (ref "K1") (pin "23") (pinfunction "23_23") (pintype "passive"))
    )
    (net (code "59") (name "unconnected-(K1-Pad24)") (class "Default")
      (node (ref "K1") (pin "24") (pinfunction "24_24") (pintype "passive"))
    )
    (net (code "60") (name "unconnected-(K1-Pad26)") (class "Default")
      (node (ref "K1") (pin "26") (pinfunction "26_26") (pintype "passive"))
    )
    (net (code "61") (name "unconnected-(K1-Pad27)") (class "Default")
      (node (ref "K1") (pin "27") (pinfunction "27_27") (pintype "passive"))
    )
    (net (code "62") (name "unconnected-(K1-Pad28)") (class "Default")
      (node (ref "K1") (pin "28") (pinfunction "28_28") (pintype "passive"))
    )
    (net (code "63") (name "unconnected-(K1-Pad29)") (class "Default")
      (node (ref "K1") (pin "29") (pinfunction "29_29") (pintype "passive"))
    )
    (net (code "64") (name "unconnected-(K1-Pad31)") (class "Default")
      (node (ref "K1") (pin "31") (pinfunction "31_31") (pintype "passive"))
    )
    (net (code "65") (name "unconnected-(K1-Pad32)") (class "Default")
      (node (ref "K1") (pin "32") (pinfunction "32_32") (pintype "passive"))
    )
    (net (code "66") (name "unconnected-(K1-Pad33)") (class "Default")
      (node (ref "K1") (pin "33") (pinfunction "33_33") (pintype "passive"))
    )
    (net (code "67") (name "unconnected-(K1-Pad35)") (class "Default")
      (node (ref "K1") (pin "35") (pinfunction "35_35") (pintype "passive"))
    )
    (net (code "68") (name "unconnected-(K1-Pad36)") (class "Default")
      (node (ref "K1") (pin "36") (pinfunction "36_36") (pintype "passive"))
    )
    (net (code "69") (name "unconnected-(K1-Pad37)") (class "Default")
      (node (ref "K1") (pin "37") (pinfunction "37_37") (pintype "passive"))
    )
    (net (code "70") (name "unconnected-(K1-Pad38)") (class "Default")
      (node (ref "K1") (pin "38") (pinfunction "38_38") (pintype "passive"))
    )
    (net (code "71") (name "unconnected-(K1-Pad40)") (class "Default")
      (node (ref "K1") (pin "40") (pinfunction "40_40") (pintype "passive"))
    )
    (net (code "72") (name "unconnected-(U1-PA02{slash}EINT2{slash}AIN0{slash}Y0{slash}VOUT1-Pad3)") (class "Default")
      (node (ref "U1") (pin "3") (pinfunction "PA02/EINT2/AIN0/Y0/VOUT1_3") (pintype "bidirectional"))
    )
    (net (code "73") (name "unconnected-(U1-PA04{slash}EINT4{slash}VREFB{slash}AIN4{slash}SERCOM0.0-Pad9)") (class "Default")
      (node (ref "U1") (pin "9") (pinfunction "PA04/EINT4/VREFB/AIN4/SERCOM0.0_9") (pintype "bidirectional"))
    )
    (net (code "74") (name "unconnected-(U1-PA06{slash}EINT6{slash}AIN6{slash}SERCOM0.2-Pad11)") (class "Default")
      (node (ref "U1") (pin "11") (pinfunction "PA06/EINT6/AIN6/SERCOM0.2_11") (pintype "bidirectional"))
    )
    (net (code "75") (name "unconnected-(U1-PA07{slash}I7{slash}AIN7{slash}SERCOM0.3{slash}I2SD0-Pad12)") (class "Default")
      (node (ref "U1") (pin "12") (pinfunction "PA07/I7/AIN7/SERCOM0.3/I2SD0_12") (pintype "bidirectional"))
    )
    (net (code "76") (name "unconnected-(U1-PA08{slash}I2C{slash}AIN16{slash}SERCOM0+2.0{slash}I2SD1-Pad13)") (class "Default")
      (node (ref "U1") (pin "13") (pinfunction "PA08/I2C/AIN16/SERCOM0+2.0/I2SD1_13") (pintype "bidirectional"))
    )
    (net (code "77") (name "unconnected-(U1-PA09{slash}I2C{slash}I9{slash}AIN17{slash}SERCOM0+2.1{slash}I2SMC-Pad14)") (class "Default")
      (node (ref "U1") (pin "14") (pinfunction "PA09/I2C/I9/AIN17/SERCOM0+2.1/I2SMC_14") (pintype "bidirectional"))
    )
    (net (code "78") (name "unconnected-(U1-PA13{slash}I13{slash}I2C{slash}SERCOM2+4.1-Pad22)") (class "Default")
      (node (ref "U1") (pin "22") (pinfunction "PA13/I13/I2C/SERCOM2+4.1_22") (pintype "bidirectional"))
    )
    (net (code "79") (name "unconnected-(U1-PA14{slash}I14{slash}SERCOM2+4.2-Pad23)") (class "Default")
      (node (ref "U1") (pin "23") (pinfunction "PA14/I14/SERCOM2+4.2_23") (pintype "bidirectional"))
    )
    (net (code "80") (name "unconnected-(U1-PA27{slash}I15-Pad39)") (class "Default")
      (node (ref "U1") (pin "39") (pinfunction "PA27/I15_39") (pintype "bidirectional"))
    )
    (net (code "81") (name "unconnected-(U1-PA28{slash}I8-Pad41)") (class "Default")
      (node (ref "U1") (pin "41") (pinfunction "PA28/I8_41") (pintype "bidirectional"))
    )
    (net (code "82") (name "unconnected-(U1-PB02{slash}I2{slash}AIN10{slash}SERCOM5.0-Pad47)") (class "Default")
      (node (ref "U1") (pin "47") (pinfunction "PB02/I2/AIN10/SERCOM5.0_47") (pintype "bidirectional"))
    )
    (net (code "83") (name "unconnected-(U1-PB03{slash}I3{slash}AIN11{slash}SERCOM5.1-Pad48)") (class "Default")
      (node (ref "U1") (pin "48") (pinfunction "PB03/I3/AIN11/SERCOM5.1_48") (pintype "bidirectional"))
    )
    (net (code "84") (name "unconnected-(U1-PB08{slash}I8{slash}AIN2{slash}SERCOM4.0-Pad7)") (class "Default")
      (node (ref "U1") (pin "7") (pinfunction "PB08/I8/AIN2/SERCOM4.0_7") (pintype "bidirectional"))
    )
    (net (code "85") (name "unconnected-(U1-PB09{slash}I9{slash}AIN3{slash}SERCOM4.1-Pad8)") (class "Default")
      (node (ref "U1") (pin "8") (pinfunction "PB09/I9/AIN3/SERCOM4.1_8") (pintype "bidirectional"))
    )
    (net (code "86") (name "unconnected-(U1-PB10{slash}I10{slash}SERCOM4.2{slash}I2SMC-Pad19)") (class "Default")
      (node (ref "U1") (pin "19") (pinfunction "PB10/I10/SERCOM4.2/I2SMC_19") (pintype "bidirectional"))
    )
    (net (code "87") (name "unconnected-(U1-PB11{slash}I11{slash}SERCOM4.3{slash}I2SCL-Pad20)") (class "Default")
      (node (ref "U1") (pin "20") (pinfunction "PB11/I11/SERCOM4.3/I2SCL_20") (pintype "bidirectional"))
    )
    (net (code "88") (name "unconnected-(U1-PB22{slash}I6{slash}SERCOM5.2-Pad37)") (class "Default")
      (node (ref "U1") (pin "37") (pinfunction "PB22/I6/SERCOM5.2_37") (pintype "bidirectional"))
    )
    (net (code "89") (name "unconnected-(U1-PB23{slash}I7{slash}SERCOM5.3-Pad38)") (class "Default")
      (node (ref "U1") (pin "38") (pinfunction "PB23/I7/SERCOM5.3_38") (pintype "bidirectional"))
    )
    (net (code "90") (name "unconnected-(U4-P4-Pad4)") (class "Default")
      (node (ref "U4") (pin "4") (pinfunction "P4_4") (pintype "bidirectional"))
    )
    (net (code "91") (name "unconnected-(X5A-S-Pad1)") (class "Default")
      (node (ref "X5") (pin "1") (pinfunction "S_1") (pintype "passive"))
    )
    (net (code "92") (name "unconnected-(X6-PadID)") (class "Default")
      (node (ref "X6") (pin "ID") (pinfunction "ID_ID") (pintype "bidirectional"))
    )
    (net (code "93") (name "{slash}RESET") (class "Default")
      (node (ref "K1") (pin "12") (pinfunction "12_12") (pintype "passive"))
      (node (ref "R1") (pin "1") (pinfunction "1_1") (pintype "passive"))
      (node (ref "RESET") (pin "3") (pinfunction "3_3") (pintype "passive"))
      (node (ref "RESET") (pin "4") (pinfunction "4_4") (pintype "passive"))
      (node (ref "U1") (pin "40") (pinfunction "~{RESETN}_40") (pintype "input"))
    )
  )
)
